# NSR_latch.net
KiCad netlist of a schematic drawn in EAGLE
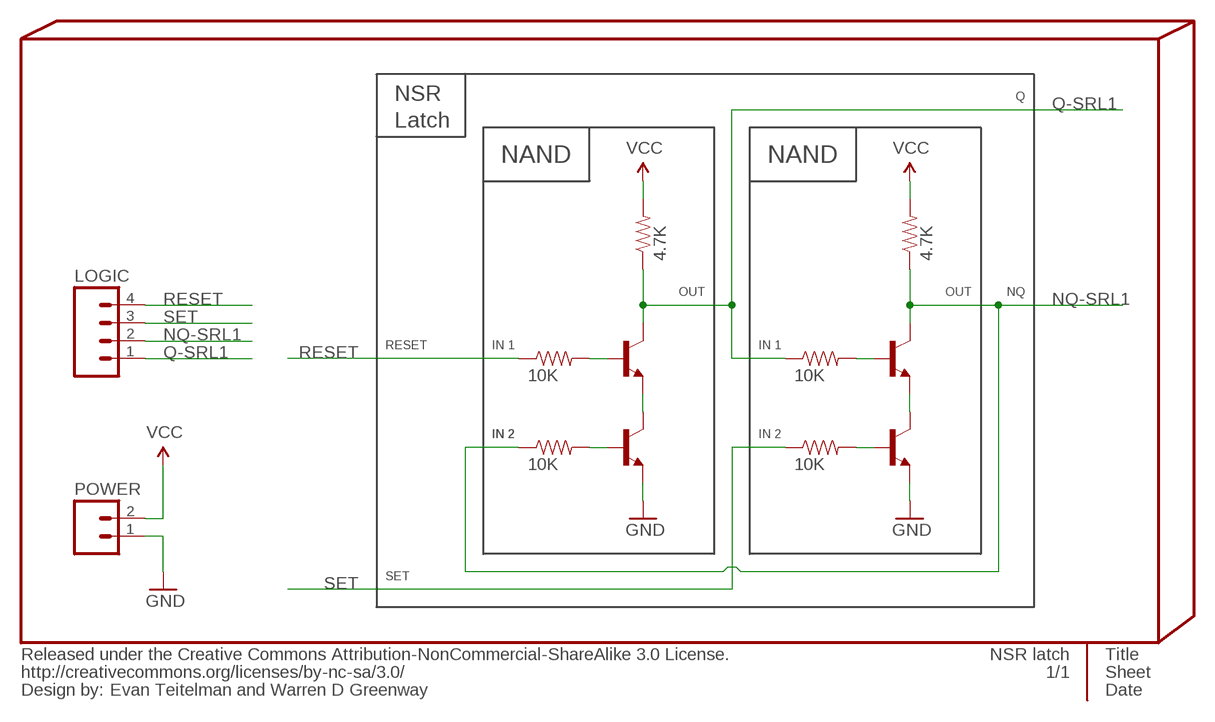
[diagram p0: schematic, sheet 1]

(export (version "E")
  (design (tool "Eeschema 10.0.6"))
  (components
    (comp (ref "INFO4")
      (value "Evan Teitelman and Warren D Greenway")
      (footprint "eagle-import:%CC-NC-SA")
      (libsource (lib "eagle-import") (part "%CC-NC-SA"))
    )
    (comp (ref "LOGIC")
      (value "M04PTH")
      (footprint "eagle-import:1X04")
      (libsource (lib "eagle-import") (part "M04PTH"))
    )
    (comp (ref "POWER")
      (value "M02PTH")
      (footprint "eagle-import:1X02")
      (libsource (lib "eagle-import") (part "M02PTH"))
    )
    (comp (ref "PUR-NAND1")
      (value "4.7K")
      (footprint "eagle-import:0402-RES")
      (libsource (lib "eagle-import") (part "RESISTOR0402-RES"))
    )
    (comp (ref "PUR-NAND2")
      (value "4.7K")
      (footprint "eagle-import:0402-RES")
      (libsource (lib "eagle-import") (part "RESISTOR0402-RES"))
    )
    (comp (ref "Q1-NAND1")
      (value "TRANSISTOR_NPNSOT23")
      (footprint "eagle-import:SOT23")
      (libsource (lib "eagle-import") (part "TRANSISTOR_NPNSOT23"))
    )
    (comp (ref "Q1-NAND2")
      (value "TRANSISTOR_NPNSOT23")
      (footprint "eagle-import:SOT23")
      (libsource (lib "eagle-import") (part "TRANSISTOR_NPNSOT23"))
    )
    (comp (ref "Q2-NAND1")
      (value "TRANSISTOR_NPNSOT23")
      (footprint "eagle-import:SOT23")
      (libsource (lib "eagle-import") (part "TRANSISTOR_NPNSOT23"))
    )
    (comp (ref "Q2-NAND2")
      (value "TRANSISTOR_NPNSOT23")
      (footprint "eagle-import:SOT23")
      (libsource (lib "eagle-import") (part "TRANSISTOR_NPNSOT23"))
    )
    (comp (ref "R1-NAND1")
      (value "10K")
      (footprint "eagle-import:0402-RES")
      (libsource (lib "eagle-import") (part "RESISTOR0402-RES"))
    )
    (comp (ref "R1-NAND2")
      (value "10K")
      (footprint "eagle-import:0402-RES")
      (libsource (lib "eagle-import") (part "RESISTOR0402-RES"))
    )
    (comp (ref "R2-NAND1")
      (value "10K")
      (footprint "eagle-import:0402-RES")
      (libsource (lib "eagle-import") (part "RESISTOR0402-RES"))
    )
    (comp (ref "R2-NAND2")
      (value "10K")
      (footprint "eagle-import:0402-RES")
      (libsource (lib "eagle-import") (part "RESISTOR0402-RES"))
    )
  )
  (nets
    (net (code "1") (name "/NQ-SRL1") (class "Default")
      (node (ref "LOGIC") (pin "2") (pinfunction "2_2") (pintype "passive"))
      (node (ref "PUR-NAND1") (pin "1") (pinfunction "1_1") (pintype "passive"))
      (node (ref "Q1-NAND1") (pin "3") (pinfunction "C_3") (pintype "passive"))
      (node (ref "R2-NAND1") (pin "1") (pinfunction "1_1") (pintype "passive"))
    )
    (net (code "2") (name "/Q-SRL1") (class "Default")
      (node (ref "LOGIC") (pin "1") (pinfunction "1_1") (pintype "passive"))
      (node (ref "PUR-NAND2") (pin "1") (pinfunction "1_1") (pintype "passive"))
      (node (ref "Q1-NAND2") (pin "3") (pinfunction "C_3") (pintype "passive"))
      (node (ref "R1-NAND1") (pin "1") (pinfunction "1_1") (pintype "passive"))
    )
    (net (code "3") (name "/RESET") (class "Default")
      (node (ref "LOGIC") (pin "4") (pinfunction "4_4") (pintype "passive"))
      (node (ref "R1-NAND2") (pin "1") (pinfunction "1_1") (pintype "passive"))
    )
    (net (code "4") (name "/SET") (class "Default")
      (node (ref "LOGIC") (pin "3") (pinfunction "3_3") (pintype "passive"))
      (node (ref "R2-NAND2") (pin "1") (pinfunction "1_1") (pintype "passive"))
    )
    (net (code "5") (name "@GND") (class "Default")
      (node (ref "POWER") (pin "1") (pinfunction "1_1") (pintype "passive"))
      (node (ref "Q2-NAND1") (pin "2") (pinfunction "E_2") (pintype "passive"))
      (node (ref "Q2-NAND2") (pin "2") (pinfunction "E_2") (pintype "passive"))
    )
    (net (code "6") (name "@VCC") (class "Default")
      (node (ref "POWER") (pin "2") (pinfunction "2_2") (pintype "passive"))
      (node (ref "PUR-NAND1") (pin "2") (pinfunction "2_2") (pintype "passive"))
      (node (ref "PUR-NAND2") (pin "2") (pinfunction "2_2") (pintype "passive"))
    )
    (net (code "7") (name "Net-(Q1-NAND1-B)") (class "Default")
      (node (ref "Q1-NAND1") (pin "1") (pinfunction "B_1") (pintype "passive"))
      (node (ref "R1-NAND1") (pin "2") (pinfunction "2_2") (pintype "passive"))
    )
    (net (code "8") (name "Net-(Q1-NAND1-E)") (class "Default")
      (node (ref "Q1-NAND1") (pin "2") (pinfunction "E_2") (pintype "passive"))
      (node (ref "Q2-NAND1") (pin "3") (pinfunction "C_3") (pintype "passive"))
    )
    (net (code "9") (name "Net-(Q1-NAND2-B)") (class "Default")
      (node (ref "Q1-NAND2") (pin "1") (pinfunction "B_1") (pintype "passive"))
      (node (ref "R1-NAND2") (pin "2") (pinfunction "2_2") (pintype "passive"))
    )
    (net (code "10") (name "Net-(Q1-NAND2-E)") (class "Default")
      (node (ref "Q1-NAND2") (pin "2") (pinfunction "E_2") (pintype "passive"))
      (node (ref "Q2-NAND2") (pin "3") (pinfunction "C_3") (pintype "passive"))
    )
    (net (code "11") (name "Net-(Q2-NAND1-B)") (class "Default")
      (node (ref "Q2-NAND1") (pin "1") (pinfunction "B_1") (pintype "passive"))
      (node (ref "R2-NAND2") (pin "2") (pinfunction "2_2") (pintype "passive"))
    )
    (net (code "12") (name "Net-(Q2-NAND2-B)") (class "Default")
      (node (ref "Q2-NAND2") (pin "1") (pinfunction "B_1") (pintype "passive"))
      (node (ref "R2-NAND1") (pin "2") (pinfunction "2_2") (pintype "passive"))
    )
  )
)
